# Acoustics_Board_Pg_2.net
KiCad netlist of a schematic drawn in Altium Designer
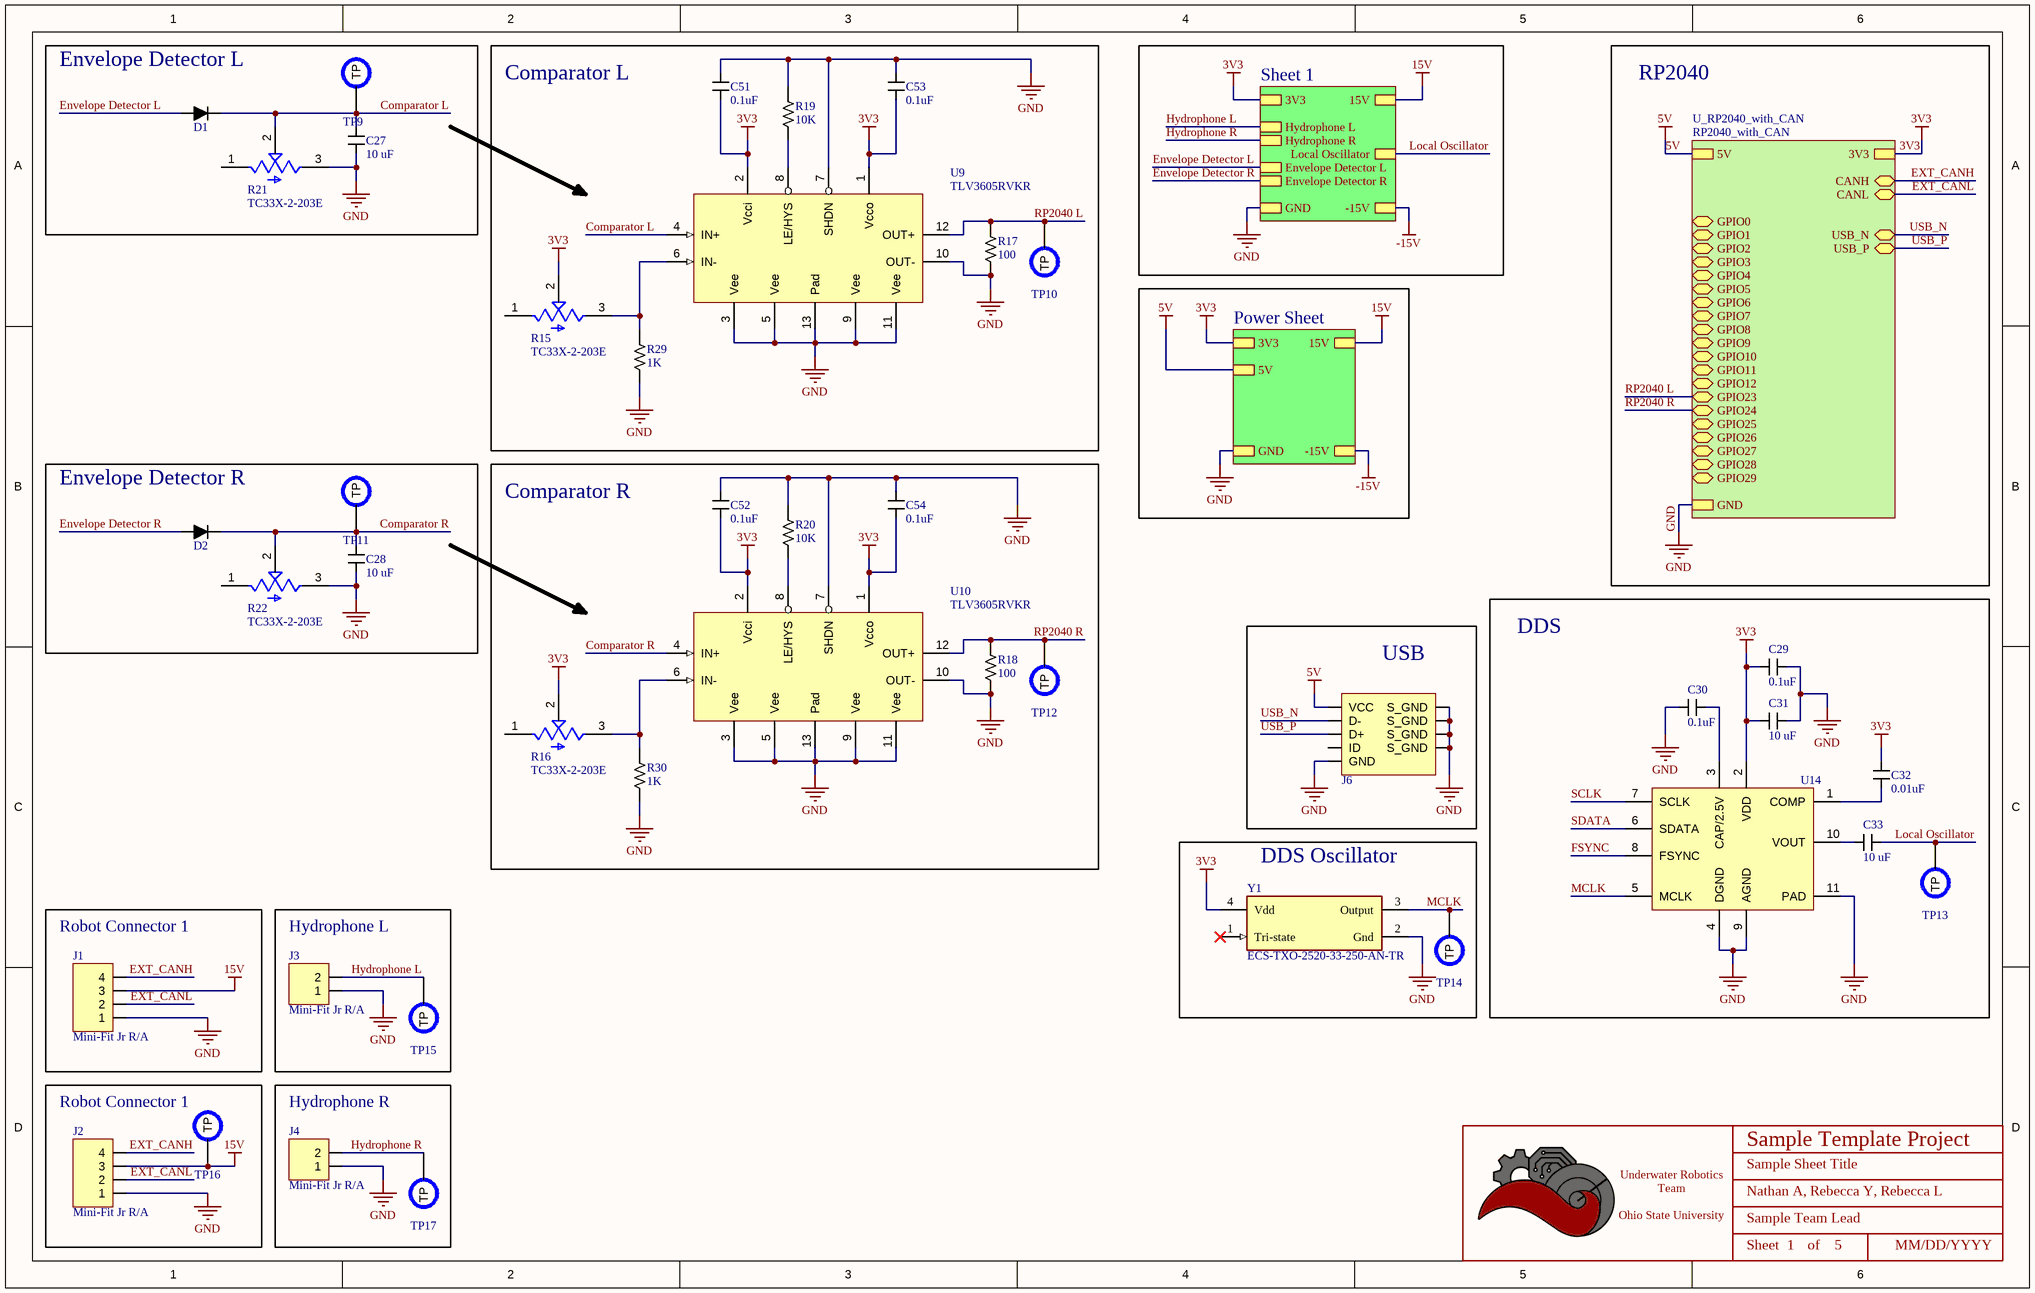
[diagram p0: Acoustics Board Pg. 2.SchDoc]

(export (version "E")
  (design (tool "Eeschema 10.0.6"))
  (components
    (comp (ref "C27")
      (value "10uF Ceramic 6.3V")
      (footprint "CAPACITOR_0603")
      (description "Cap 10uF 6.3V +/-20%\r\nCeramic 0603")
      (fields
        (field (name "TOLERANCE") "+/- 20%")
        (field (name "VOLTAGE") "6.3V")
        (field (name "VALUE (UF)") "10 uF")
        (field (name "MADE BY") "Flip B")
      )
      (libsource (lib "Capacitors") (part "CAPACITOR_10uF_0603"))
    )
    (comp (ref "C28")
      (value "10uF Ceramic 6.3V")
      (footprint "CAPACITOR_0603")
      (description "Cap 10uF 6.3V +/-20%\r\nCeramic 0603")
      (fields
        (field (name "TOLERANCE") "+/- 20%")
        (field (name "VOLTAGE") "6.3V")
        (field (name "VALUE (UF)") "10 uF")
        (field (name "MADE BY") "Flip B")
      )
      (libsource (lib "Capacitors") (part "CAPACITOR_10uF_0603"))
    )
    (comp (ref "C29")
      (value "0.1uF")
      (footprint "CAPACITOR_0603")
      (description "Cap 100nF 6.3V +/-10%\r\nCeramic 0603")
      (fields
        (field (name "TOLERANCE") "+/- 10%")
        (field (name "VOLTAGE") "6.3V")
        (field (name "MADE BY") "Flip B")
      )
      (libsource (lib "Capacitors") (part "CAPACITOR_0.1uF_0603"))
    )
    (comp (ref "C30")
      (value "0.1uF")
      (footprint "CAPACITOR_0603")
      (description "Cap 100nF 6.3V +/-10%\r\nCeramic 0603")
      (fields
        (field (name "TOLERANCE") "+/- 10%")
        (field (name "VOLTAGE") "6.3V")
        (field (name "MADE BY") "Flip B")
      )
      (libsource (lib "Capacitors") (part "CAPACITOR_0.1uF_0603"))
    )
    (comp (ref "C31")
      (value "10uF Ceramic 6.3V")
      (footprint "CAPACITOR_0603")
      (description "Cap 10uF 6.3V +/-20%\r\nCeramic 0603")
      (fields
        (field (name "TOLERANCE") "+/- 20%")
        (field (name "VOLTAGE") "6.3V")
        (field (name "VALUE (UF)") "10 uF")
        (field (name "MADE BY") "Flip B")
      )
      (libsource (lib "Capacitors") (part "CAPACITOR_10uF_0603"))
    )
    (comp (ref "C32")
      (value "0.01uF")
      (footprint "CAPACITOR_0603")
      (description "10000 pF ±10% 50V Ceramic Capacitor X7R 0603 (1608 Metric)")
      (fields
        (field (name "TOLERANCE") "+/- 10%")
        (field (name "VOLTAGE") "6.3V")
        (field (name "MADE BY") "Flip B")
      )
      (libsource (lib "Capacitors") (part "CAPACITOR_0.01uF_0603_50V"))
    )
    (comp (ref "C33")
      (value "10uF Ceramic 6.3V")
      (footprint "CAPACITOR_0603")
      (description "Cap 10uF 6.3V +/-20%\r\nCeramic 0603")
      (fields
        (field (name "TOLERANCE") "+/- 20%")
        (field (name "VOLTAGE") "6.3V")
        (field (name "VALUE (UF)") "10 uF")
        (field (name "MADE BY") "Flip B")
      )
      (libsource (lib "Capacitors") (part "CAPACITOR_10uF_0603"))
    )
    (comp (ref "C51")
      (value "0.1uF")
      (footprint "CAPACITOR_0603")
      (description "Cap 100nF 6.3V +/-10%\r\nCeramic 0603")
      (fields
        (field (name "TOLERANCE") "+/- 10%")
        (field (name "VOLTAGE") "6.3V")
        (field (name "MADE BY") "Flip B")
      )
      (libsource (lib "Capacitors") (part "CAPACITOR_0.1uF_0603"))
    )
    (comp (ref "C52")
      (value "0.1uF")
      (footprint "CAPACITOR_0603")
      (description "Cap 100nF 6.3V +/-10%\r\nCeramic 0603")
      (fields
        (field (name "TOLERANCE") "+/- 10%")
        (field (name "VOLTAGE") "6.3V")
        (field (name "MADE BY") "Flip B")
      )
      (libsource (lib "Capacitors") (part "CAPACITOR_0.1uF_0603"))
    )
    (comp (ref "C53")
      (value "0.1uF")
      (footprint "CAPACITOR_0603")
      (description "Cap 100nF 6.3V +/-10%\r\nCeramic 0603")
      (fields
        (field (name "TOLERANCE") "+/- 10%")
        (field (name "VOLTAGE") "6.3V")
        (field (name "MADE BY") "Flip B")
      )
      (libsource (lib "Capacitors") (part "CAPACITOR_0.1uF_0603"))
    )
    (comp (ref "C54")
      (value "0.1uF")
      (footprint "CAPACITOR_0603")
      (description "Cap 100nF 6.3V +/-10%\r\nCeramic 0603")
      (fields
        (field (name "TOLERANCE") "+/- 10%")
        (field (name "VOLTAGE") "6.3V")
        (field (name "MADE BY") "Flip B")
      )
      (libsource (lib "Capacitors") (part "CAPACITOR_0.1uF_0603"))
    )
    (comp (ref "D1")
      (value "BAR9002ELE6327XTMA1")
      (footprint "DIODE_0402")
      (description "RF Diode PIN - Single 80V 100 mA 250 mW PG-TSLP-2-19")
      (libsource (lib "Diodes") (part "RF Diode 80V 100mA"))
    )
    (comp (ref "D2")
      (value "BAR9002ELE6327XTMA1")
      (footprint "DIODE_0402")
      (description "RF Diode PIN - Single 80V 100 mA 250 mW PG-TSLP-2-19")
      (libsource (lib "Diodes") (part "RF Diode 80V 100mA"))
    )
    (comp (ref "J1")
      (value "Mini-Fit Jr R/A")
      (footprint "CONN_MOLEX_MINIFIT JR_4 POS_R/A")
      (description "Molex Minifit Jr. 5569 \r\n4 Pos R/A Natural")
      (fields (field (name "MANUFACTURER") "Molex") (field (name "CREATED BY") "Flip B"))
      (libsource (lib "Connectors") (part "CONN_MOLEX_MINIFIT JR_4POS_R/A"))
    )
    (comp (ref "J2")
      (value "Mini-Fit Jr R/A")
      (footprint "CONN_MOLEX_MINIFIT JR_4 POS_R/A")
      (description "Molex Minifit Jr. 5569 \r\n4 Pos R/A Natural")
      (fields (field (name "MANUFACTURER") "Molex") (field (name "CREATED BY") "Flip B"))
      (libsource (lib "Connectors") (part "CONN_MOLEX_MINIFIT JR_4POS_R/A"))
    )
    (comp (ref "J3")
      (value "Mini-Fit Jr R/A")
      (footprint "CONN_MOLEX_MINIFIT JR_2 POS_R/A")
      (description "Molex Minifit Jr. 5569 \r\n2 Pos R/A Natural")
      (fields (field (name "MANUFACTURER") "Molex") (field (name "CREATED BY") "Robert P"))
      (libsource (lib "Connectors") (part "CONN_MOLEX_MINIFIT JR_2POS_R/A"))
    )
    (comp (ref "J4")
      (value "Mini-Fit Jr R/A")
      (footprint "CONN_MOLEX_MINIFIT JR_2 POS_R/A")
      (description "Molex Minifit Jr. 5569 \r\n2 Pos R/A Natural")
      (fields (field (name "MANUFACTURER") "Molex") (field (name "CREATED BY") "Robert P"))
      (libsource (lib "Connectors") (part "CONN_MOLEX_MINIFIT JR_2POS_R/A"))
    )
    (comp (ref "J6")
      (value "USB_MICRO R/A")
      (footprint "CONN_MINIUSB")
      (description "Amphenol Micro USB-B\r\nUSB2.0 5 Pin Right Angle SMD")
      (fields (field (name "MANUFACTURER") "Amphenol") (field (name "CREATED BY") "Flip B"))
      (libsource (lib "Connectors") (part "CONN_MICROUSB"))
    )
    (comp (ref "R15")
      (value "TC33X-2-203E")
      (footprint "TRIM_TC33X-2-203E")
      (description "20 kOhms 0.1W, 1/10W J Lead Surface Mount Trimmer Potentiometer Cermet 1 Turn Top Adjustment")
      (fields (field (name "MF") "Bourns") (field (name "DIGI-KEY_PART_NUMBER") "TC33X-2-203ECT-ND"))
      (libsource (lib "Resistors") (part "TC33X-2-203E"))
    )
    (comp (ref "R16")
      (value "TC33X-2-203E")
      (footprint "TRIM_TC33X-2-203E")
      (description "20 kOhms 0.1W, 1/10W J Lead Surface Mount Trimmer Potentiometer Cermet 1 Turn Top Adjustment")
      (fields (field (name "MF") "Bourns") (field (name "DIGI-KEY_PART_NUMBER") "TC33X-2-203ECT-ND"))
      (libsource (lib "Resistors") (part "TC33X-2-203E"))
    )
    (comp (ref "R17")
      (value "100 Ohm 5% 1/8W")
      (footprint "RESISTOR_0603")
      (description "RES 100 OHM 5% 1/8W 0603")
      (fields
        (field (name "TOLERANCE") "+/- 5%")
        (field (name "VALUE  (OHMS)") "100")
        (field (name "MADE BY") "Flip B")
      )
      (libsource (lib "Resistors") (part "RESISTOR_100_0603_1"))
    )
    (comp (ref "R18")
      (value "100 Ohm 5% 1/8W")
      (footprint "RESISTOR_0603")
      (description "RES 100 OHM 5% 1/8W 0603")
      (fields
        (field (name "TOLERANCE") "+/- 5%")
        (field (name "VALUE  (OHMS)") "100")
        (field (name "MADE BY") "Flip B")
      )
      (libsource (lib "Resistors") (part "RESISTOR_100_0603_1"))
    )
    (comp (ref "R19")
      (value "10k Ohm 5% 1/10W")
      (footprint "RESISTOR_0603")
      (description "RES 10k OHM 5% 1/10W 0603")
      (fields
        (field (name "TOLERANCE") "+/- 5%")
        (field (name "VALUE  (OHMS)") "10K")
        (field (name "MADE BY") "Robert Pafford")
      )
      (libsource (lib "Resistors") (part "RESISTOR_10K_0603"))
    )
    (comp (ref "R20")
      (value "10k Ohm 5% 1/10W")
      (footprint "RESISTOR_0603")
      (description "RES 10k OHM 5% 1/10W 0603")
      (fields
        (field (name "TOLERANCE") "+/- 5%")
        (field (name "VALUE  (OHMS)") "10K")
        (field (name "MADE BY") "Robert Pafford")
      )
      (libsource (lib "Resistors") (part "RESISTOR_10K_0603"))
    )
    (comp (ref "R21")
      (value "TC33X-2-203E")
      (footprint "TRIM_TC33X-2-203E")
      (description "20 kOhms 0.1W, 1/10W J Lead Surface Mount Trimmer Potentiometer Cermet 1 Turn Top Adjustment")
      (fields (field (name "MF") "Bourns") (field (name "DIGI-KEY_PART_NUMBER") "TC33X-2-203ECT-ND"))
      (libsource (lib "Resistors") (part "TC33X-2-203E"))
    )
    (comp (ref "R22")
      (value "TC33X-2-203E")
      (footprint "TRIM_TC33X-2-203E")
      (description "20 kOhms 0.1W, 1/10W J Lead Surface Mount Trimmer Potentiometer Cermet 1 Turn Top Adjustment")
      (fields (field (name "MF") "Bourns") (field (name "DIGI-KEY_PART_NUMBER") "TC33X-2-203ECT-ND"))
      (libsource (lib "Resistors") (part "TC33X-2-203E"))
    )
    (comp (ref "R29")
      (value "1k Ohm 5% 1/10W")
      (footprint "RESISTOR_0603")
      (description "RES 1k OHM 0.5% 1/10W 0603")
      (fields
        (field (name "TOLERANCE") "+/- 0.5%")
        (field (name "VALUE  (OHMS)") "1K")
        (field (name "MADE BY") "Robert Pafford")
      )
      (libsource (lib "Resistors") (part "RESISTOR_1K_0.5%_0603"))
    )
    (comp (ref "R30")
      (value "1k Ohm 5% 1/10W")
      (footprint "RESISTOR_0603")
      (description "RES 1k OHM 0.5% 1/10W 0603")
      (fields
        (field (name "TOLERANCE") "+/- 0.5%")
        (field (name "VALUE  (OHMS)") "1K")
        (field (name "MADE BY") "Robert Pafford")
      )
      (libsource (lib "Resistors") (part "RESISTOR_1K_0.5%_0603"))
    )
    (comp (ref "TP9")
      (value "PCB Test Point")
      (footprint "TESTPOINT_1.2MM")
      (fields (field (name "MADE BY") "Robert Pafford"))
      (libsource (lib "Connectors") (part "TESTPOINT"))
    )
    (comp (ref "TP10")
      (value "PCB Test Point")
      (footprint "TESTPOINT_1.2MM")
      (fields (field (name "MADE BY") "Robert Pafford"))
      (libsource (lib "Connectors") (part "TESTPOINT"))
    )
    (comp (ref "TP11")
      (value "PCB Test Point")
      (footprint "TESTPOINT_1.2MM")
      (fields (field (name "MADE BY") "Robert Pafford"))
      (libsource (lib "Connectors") (part "TESTPOINT"))
    )
    (comp (ref "TP12")
      (value "PCB Test Point")
      (footprint "TESTPOINT_1.2MM")
      (fields (field (name "MADE BY") "Robert Pafford"))
      (libsource (lib "Connectors") (part "TESTPOINT"))
    )
    (comp (ref "TP13")
      (value "PCB Test Point")
      (footprint "TESTPOINT_1.2MM")
      (fields (field (name "MADE BY") "Robert Pafford"))
      (libsource (lib "Connectors") (part "TESTPOINT"))
    )
    (comp (ref "TP14")
      (value "PCB Test Point")
      (footprint "TESTPOINT_1.2MM")
      (fields (field (name "MADE BY") "Robert Pafford"))
      (libsource (lib "Connectors") (part "TESTPOINT"))
    )
    (comp (ref "TP15")
      (value "PCB Test Point")
      (footprint "TESTPOINT_1.2MM")
      (fields (field (name "MADE BY") "Robert Pafford"))
      (libsource (lib "Connectors") (part "TESTPOINT"))
    )
    (comp (ref "TP16")
      (value "PCB Test Point")
      (footprint "TESTPOINT_1.2MM")
      (fields (field (name "MADE BY") "Robert Pafford"))
      (libsource (lib "Connectors") (part "TESTPOINT"))
    )
    (comp (ref "TP17")
      (value "PCB Test Point")
      (footprint "TESTPOINT_1.2MM")
      (fields (field (name "MADE BY") "Robert Pafford"))
      (libsource (lib "Connectors") (part "TESTPOINT"))
    )
    (comp (ref "U9")
      (value "TLV3605RVKR")
      (footprint "TLV3605RVKR")
      (description "IC COMPARATOR 1 GEN PUR 12WQFN")
      (fields (field (name "MANUFACTURER") "Texas Instruments") (field (name "CREATED BY") "Nathan Ayer"))
      (libsource (lib "Integrated Circuits") (part "TLV3605RVKR"))
    )
    (comp (ref "U10")
      (value "TLV3605RVKR")
      (footprint "TLV3605RVKR")
      (description "IC COMPARATOR 1 GEN PUR 12WQFN")
      (fields (field (name "MANUFACTURER") "Texas Instruments") (field (name "CREATED BY") "Nathan Ayer"))
      (libsource (lib "Integrated Circuits") (part "TLV3605RVKR"))
    )
    (comp (ref "U14")
      (value "IC DDS 5MHZ 10BIT 10LFCSP")
      (footprint "CP-10-9")
      (description "Direct Digital Synthesis IC 10 b 5 MHz 28 b Tuning 10-LFCSP-WD (3x3)")
      (libsource (lib "Integrated Circuits") (part "AD9837ACPZ"))
    )
    (comp (ref "Y1")
      (value "ECS-TXO-2520-33-250-AN-TR")
      (footprint "FP-ECS-TXO-2520-MFG")
      (description "XTAL OSC TCXO 25.0000MHZ HCMOS")
      (libsource (lib "Altium Content Vault") (part "04cd953f3cf158082f8c09fbdb924ef"))
    )
  )
  (nets
    (net (code "2") (name "/Comparator L") (class "Default")
      (node (ref "C27") (pin "1") (pinfunction "1_1") (pintype "passive"))
      (node (ref "D1") (pin "2") (pinfunction "2_2") (pintype "passive"))
      (node (ref "R21") (pin "2") (pinfunction "W_2") (pintype "passive"))
      (node (ref "TP9") (pin "TP") (pinfunction "TP_TP") (pintype "passive"))
      (node (ref "U9") (pin "4") (pinfunction "IN+_4") (pintype "input"))
    )
    (net (code "3") (name "/Comparator R") (class "Default")
      (node (ref "C28") (pin "1") (pinfunction "1_1") (pintype "passive"))
      (node (ref "D2") (pin "2") (pinfunction "2_2") (pintype "passive"))
      (node (ref "R22") (pin "2") (pinfunction "W_2") (pintype "passive"))
      (node (ref "TP11") (pin "TP") (pinfunction "TP_TP") (pintype "passive"))
      (node (ref "U10") (pin "4") (pinfunction "IN+_4") (pintype "input"))
    )
    (net (code "4") (name "/EXT_CANH") (class "Default")
      (node (ref "J1") (pin "4") (pinfunction "4_4") (pintype "passive"))
      (node (ref "J2") (pin "4") (pinfunction "4_4") (pintype "passive"))
    )
    (net (code "5") (name "/EXT_CANL") (class "Default")
      (node (ref "J1") (pin "2") (pinfunction "2_2") (pintype "passive"))
      (node (ref "J2") (pin "2") (pinfunction "2_2") (pintype "passive"))
    )
    (net (code "6") (name "/Envelope Detector L") (class "Default")
      (node (ref "D1") (pin "1") (pinfunction "1_1") (pintype "passive"))
    )
    (net (code "7") (name "/Envelope Detector R") (class "Default")
      (node (ref "D2") (pin "1") (pinfunction "1_1") (pintype "passive"))
    )
    (net (code "8") (name "/FSYNC") (class "Default")
      (node (ref "U14") (pin "8") (pinfunction "FSYNC_8") (pintype "passive"))
    )
    (net (code "27") (name "/Hydrophone L") (class "Default")
      (node (ref "J3") (pin "2") (pinfunction "2_2") (pintype "passive"))
      (node (ref "TP15") (pin "TP") (pinfunction "TP_TP") (pintype "passive"))
    )
    (net (code "28") (name "/Hydrophone R") (class "Default")
      (node (ref "J4") (pin "2") (pinfunction "2_2") (pintype "passive"))
      (node (ref "TP17") (pin "TP") (pinfunction "TP_TP") (pintype "passive"))
    )
    (net (code "29") (name "/Local Oscillator") (class "Default")
      (node (ref "C33") (pin "2") (pinfunction "2_2") (pintype "passive"))
      (node (ref "TP13") (pin "TP") (pinfunction "TP_TP") (pintype "passive"))
    )
    (net (code "30") (name "/MCLK") (class "Default")
      (node (ref "TP14") (pin "TP") (pinfunction "TP_TP") (pintype "passive"))
      (node (ref "U14") (pin "5") (pinfunction "MCLK_5") (pintype "passive"))
      (node (ref "Y1") (pin "3") (pinfunction "Output_3") (pintype "tri_state"))
    )
    (net (code "31") (name "/RP2040 L") (class "Default")
      (node (ref "R17") (pin "1") (pinfunction "1_1") (pintype "passive"))
      (node (ref "TP10") (pin "TP") (pinfunction "TP_TP") (pintype "passive"))
      (node (ref "U9") (pin "12") (pinfunction "OUT+_12") (pintype "passive"))
    )
    (net (code "32") (name "/RP2040 R") (class "Default")
      (node (ref "R18") (pin "1") (pinfunction "1_1") (pintype "passive"))
      (node (ref "TP12") (pin "TP") (pinfunction "TP_TP") (pintype "passive"))
      (node (ref "U10") (pin "12") (pinfunction "OUT+_12") (pintype "passive"))
    )
    (net (code "33") (name "/SCLK") (class "Default")
      (node (ref "U14") (pin "7") (pinfunction "SCLK_7") (pintype "passive"))
    )
    (net (code "34") (name "/SDATA") (class "Default")
      (node (ref "U14") (pin "6") (pinfunction "SDATA_6") (pintype "passive"))
    )
    (net (code "35") (name "/USB_N") (class "Default")
      (node (ref "J6") (pin "2") (pinfunction "D-_2") (pintype "passive"))
    )
    (net (code "36") (name "/USB_P") (class "Default")
      (node (ref "J6") (pin "3") (pinfunction "D+_3") (pintype "passive"))
    )
    (net (code "37") (name "3V3") (class "Default")
      (node (ref "C29") (pin "2") (pinfunction "2_2") (pintype "passive"))
      (node (ref "C31") (pin "1") (pinfunction "1_1") (pintype "passive"))
      (node (ref "C32") (pin "1") (pinfunction "1_1") (pintype "passive"))
      (node (ref "C51") (pin "1") (pinfunction "1_1") (pintype "passive"))
      (node (ref "C52") (pin "1") (pinfunction "1_1") (pintype "passive"))
      (node (ref "C53") (pin "1") (pinfunction "1_1") (pintype "passive"))
      (node (ref "C54") (pin "1") (pinfunction "1_1") (pintype "passive"))
      (node (ref "R15") (pin "2") (pinfunction "W_2") (pintype "passive"))
      (node (ref "R16") (pin "2") (pinfunction "W_2") (pintype "passive"))
      (node (ref "U10") (pin "1") (pinfunction "Vcco_1") (pintype "power_in"))
      (node (ref "U10") (pin "2") (pinfunction "Vcci_2") (pintype "power_in"))
      (node (ref "U14") (pin "2") (pinfunction "VDD_2") (pintype "passive"))
      (node (ref "U9") (pin "1") (pinfunction "Vcco_1") (pintype "power_in"))
      (node (ref "U9") (pin "2") (pinfunction "Vcci_2") (pintype "power_in"))
      (node (ref "Y1") (pin "4") (pinfunction "Vdd_4") (pintype "power_in"))
    )
    (net (code "38") (name "5V") (class "Default")
      (node (ref "J6") (pin "1") (pinfunction "VCC_1") (pintype "passive"))
    )
    (net (code "39") (name "15V") (class "Default")
      (node (ref "J1") (pin "3") (pinfunction "3_3") (pintype "passive"))
      (node (ref "J2") (pin "3") (pinfunction "3_3") (pintype "passive"))
      (node (ref "TP16") (pin "TP") (pinfunction "TP_TP") (pintype "passive"))
    )
    (net (code "40") (name "GND") (class "Default")
      (node (ref "C27") (pin "2") (pinfunction "2_2") (pintype "passive"))
      (node (ref "C28") (pin "2") (pinfunction "2_2") (pintype "passive"))
      (node (ref "C29") (pin "1") (pinfunction "1_1") (pintype "passive"))
      (node (ref "C30") (pin "1") (pinfunction "1_1") (pintype "passive"))
      (node (ref "C31") (pin "2") (pinfunction "2_2") (pintype "passive"))
      (node (ref "C51") (pin "2") (pinfunction "2_2") (pintype "passive"))
      (node (ref "C52") (pin "2") (pinfunction "2_2") (pintype "passive"))
      (node (ref "C53") (pin "2") (pinfunction "2_2") (pintype "passive"))
      (node (ref "C54") (pin "2") (pinfunction "2_2") (pintype "passive"))
      (node (ref "J1") (pin "1") (pinfunction "1_1") (pintype "passive"))
      (node (ref "J2") (pin "1") (pinfunction "1_1") (pintype "passive"))
      (node (ref "J3") (pin "1") (pinfunction "1_1") (pintype "passive"))
      (node (ref "J4") (pin "1") (pinfunction "1_1") (pintype "passive"))
      (node (ref "J6") (pin "5") (pinfunction "GND_5") (pintype "passive"))
      (node (ref "J6") (pin "6") (pinfunction "S_GND_6") (pintype "passive"))
      (node (ref "J6") (pin "7") (pinfunction "S_GND_7") (pintype "passive"))
      (node (ref "J6") (pin "8") (pinfunction "S_GND_8") (pintype "passive"))
      (node (ref "J6") (pin "9") (pinfunction "S_GND_9") (pintype "passive"))
      (node (ref "R17") (pin "2") (pinfunction "2_2") (pintype "passive"))
      (node (ref "R18") (pin "2") (pinfunction "2_2") (pintype "passive"))
      (node (ref "R19") (pin "1") (pinfunction "1_1") (pintype "passive"))
      (node (ref "R20") (pin "1") (pinfunction "1_1") (pintype "passive"))
      (node (ref "R21") (pin "3") (pinfunction "CW_3") (pintype "passive"))
      (node (ref "R22") (pin "3") (pinfunction "CW_3") (pintype "passive"))
      (node (ref "R29") (pin "2") (pinfunction "2_2") (pintype "passive"))
      (node (ref "R30") (pin "2") (pinfunction "2_2") (pintype "passive"))
      (node (ref "U10") (pin "10") (pinfunction "OUT-_10") (pintype "passive"))
      (node (ref "U10") (pin "11") (pinfunction "Vee_11") (pintype "power_in"))
      (node (ref "U10") (pin "13") (pinfunction "Pad_13") (pintype "power_in"))
      (node (ref "U10") (pin "3") (pinfunction "Vee_3") (pintype "power_in"))
      (node (ref "U10") (pin "5") (pinfunction "Vee_5") (pintype "power_in"))
      (node (ref "U10") (pin "7") (pinfunction "SHDN_7") (pintype "passive"))
      (node (ref "U10") (pin "9") (pinfunction "Vee_9") (pintype "power_in"))
      (node (ref "U14") (pin "11") (pinfunction "PAD_11") (pintype "passive"))
      (node (ref "U14") (pin "4") (pinfunction "DGND_4") (pintype "passive"))
      (node (ref "U14") (pin "9") (pinfunction "AGND_9") (pintype "passive"))
      (node (ref "U9") (pin "10") (pinfunction "OUT-_10") (pintype "passive"))
      (node (ref "U9") (pin "11") (pinfunction "Vee_11") (pintype "power_in"))
      (node (ref "U9") (pin "13") (pinfunction "Pad_13") (pintype "power_in"))
      (node (ref "U9") (pin "3") (pinfunction "Vee_3") (pintype "power_in"))
      (node (ref "U9") (pin "5") (pinfunction "Vee_5") (pintype "power_in"))
      (node (ref "U9") (pin "7") (pinfunction "SHDN_7") (pintype "passive"))
      (node (ref "U9") (pin "9") (pinfunction "Vee_9") (pintype "power_in"))
      (node (ref "Y1") (pin "2") (pinfunction "Gnd_2") (pintype "power_in"))
    )
    (net (code "41") (name "Net-(R15-CW)") (class "Default")
      (node (ref "R15") (pin "3") (pinfunction "CW_3") (pintype "passive"))
      (node (ref "R29") (pin "1") (pinfunction "1_1") (pintype "passive"))
      (node (ref "U9") (pin "6") (pinfunction "IN-_6") (pintype "input"))
    )
    (net (code "42") (name "Net-(R16-CW)") (class "Default")
      (node (ref "R16") (pin "3") (pinfunction "CW_3") (pintype "passive"))
      (node (ref "R30") (pin "1") (pinfunction "1_1") (pintype "passive"))
      (node (ref "U10") (pin "6") (pinfunction "IN-_6") (pintype "input"))
    )
    (net (code "43") (name "Net-(U9-LE{slash}HYS)") (class "Default")
      (node (ref "R19") (pin "2") (pinfunction "2_2") (pintype "passive"))
      (node (ref "U9") (pin "8") (pinfunction "LE/HYS_8") (pintype "passive"))
    )
    (net (code "44") (name "Net-(U10-LE{slash}HYS)") (class "Default")
      (node (ref "R20") (pin "2") (pinfunction "2_2") (pintype "passive"))
      (node (ref "U10") (pin "8") (pinfunction "LE/HYS_8") (pintype "passive"))
    )
    (net (code "45") (name "Net-(U14-CAP{slash}2.5V)") (class "Default")
      (node (ref "C30") (pin "2") (pinfunction "2_2") (pintype "passive"))
      (node (ref "U14") (pin "3") (pinfunction "CAP/2.5V_3") (pintype "passive"))
    )
    (net (code "46") (name "Net-(U14-COMP)") (class "Default")
      (node (ref "C32") (pin "2") (pinfunction "2_2") (pintype "passive"))
      (node (ref "U14") (pin "1") (pinfunction "COMP_1") (pintype "passive"))
    )
    (net (code "47") (name "Net-(U14-VOUT)") (class "Default")
      (node (ref "C33") (pin "1") (pinfunction "1_1") (pintype "passive"))
      (node (ref "U14") (pin "10") (pinfunction "VOUT_10") (pintype "passive"))
    )
    (net (code "48") (name "unconnected-(J6-ID-Pad4)") (class "Default")
      (node (ref "J6") (pin "4") (pinfunction "ID_4") (pintype "passive"))
    )
    (net (code "49") (name "unconnected-(R15-CCW-Pad1)") (class "Default")
      (node (ref "R15") (pin "1") (pinfunction "CCW_1") (pintype "passive"))
    )
    (net (code "50") (name "unconnected-(R16-CCW-Pad1)") (class "Default")
      (node (ref "R16") (pin "1") (pinfunction "CCW_1") (pintype "passive"))
    )
    (net (code "51") (name "unconnected-(R21-CCW-Pad1)") (class "Default")
      (node (ref "R21") (pin "1") (pinfunction "CCW_1") (pintype "passive"))
    )
    (net (code "52") (name "unconnected-(R22-CCW-Pad1)") (class "Default")
      (node (ref "R22") (pin "1") (pinfunction "CCW_1") (pintype "passive"))
    )
    (net (code "53") (name "unconnected-(Y1-Tri-state-Pad1)") (class "Default")
      (node (ref "Y1") (pin "1") (pinfunction "Tri-state_1") (pintype "input+no_connect"))
    )
  )
)
